# CDRon_IMU-BAT.net
KiCad netlist of a schematic drawn in Altium Designer
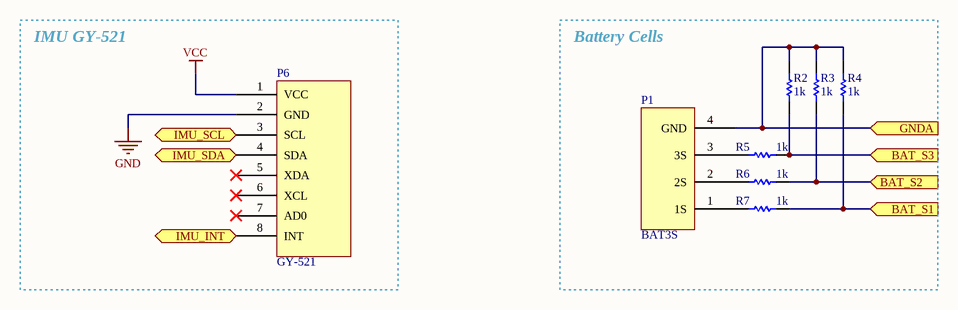
[diagram p0: CDRon_IMU-BAT.SchDoc]

(export (version "E")
  (design (tool "Eeschema 10.0.6"))
  (components
    (comp (ref "P1") (value "BAT3S") (footprint "BAT3S") (libsource (lib "CDRon_lib") (part "BAT3S")))
    (comp (ref "P6") (value "GY-521") (footprint "GY-521") (libsource (lib "CDRon_lib") (part "GY-521")))
    (comp (ref "R2")
      (value "1k")
      (footprint "R 1206")
      (description "Resistencia")
      (fields (field (name ".CREATOR") "SR"))
      (libsource (lib "CDRon_lib") (part "R"))
    )
    (comp (ref "R3")
      (value "1k")
      (footprint "R 1206")
      (description "Resistencia")
      (fields (field (name ".CREATOR") "SR"))
      (libsource (lib "CDRon_lib") (part "R"))
    )
    (comp (ref "R4")
      (value "1k")
      (footprint "R 1206")
      (description "Resistencia")
      (fields (field (name ".CREATOR") "SR"))
      (libsource (lib "CDRon_lib") (part "R"))
    )
    (comp (ref "R5")
      (value "1k")
      (footprint "R 1206")
      (description "Resistencia")
      (fields (field (name ".CREATOR") "SR"))
      (libsource (lib "CDRon_lib") (part "R"))
    )
    (comp (ref "R6")
      (value "1k")
      (footprint "R 1206")
      (description "Resistencia")
      (fields (field (name ".CREATOR") "SR"))
      (libsource (lib "CDRon_lib") (part "R"))
    )
    (comp (ref "R7")
      (value "1k")
      (footprint "R 1206")
      (description "Resistencia")
      (fields (field (name ".CREATOR") "SR"))
      (libsource (lib "CDRon_lib") (part "R"))
    )
  )
  (nets
    (net (code "1") (name "/BAT_S1") (class "Default")
      (node (ref "R4") (pin "1") (pinfunction "1_1") (pintype "passive"))
      (node (ref "R7") (pin "2") (pinfunction "2_2") (pintype "passive"))
    )
    (net (code "2") (name "/BAT_S2") (class "Default")
      (node (ref "R3") (pin "1") (pinfunction "1_1") (pintype "passive"))
      (node (ref "R6") (pin "2") (pinfunction "2_2") (pintype "passive"))
    )
    (net (code "3") (name "/BAT_S3") (class "Default")
      (node (ref "R2") (pin "1") (pinfunction "1_1") (pintype "passive"))
      (node (ref "R5") (pin "2") (pinfunction "2_2") (pintype "passive"))
    )
    (net (code "4") (name "/GNDA") (class "Default")
      (node (ref "P1") (pin "4") (pinfunction "GND_4") (pintype "passive"))
      (node (ref "R2") (pin "2") (pinfunction "2_2") (pintype "passive"))
      (node (ref "R3") (pin "2") (pinfunction "2_2") (pintype "passive"))
      (node (ref "R4") (pin "2") (pinfunction "2_2") (pintype "passive"))
    )
    (net (code "5") (name "/IMU_INT") (class "Default")
      (node (ref "P6") (pin "8") (pinfunction "INT_8") (pintype "passive"))
    )
    (net (code "6") (name "/IMU_SCL") (class "Default")
      (node (ref "P6") (pin "3") (pinfunction "SCL_3") (pintype "passive"))
    )
    (net (code "7") (name "/IMU_SDA") (class "Default")
      (node (ref "P6") (pin "4") (pinfunction "SDA_4") (pintype "passive"))
    )
    (net (code "8") (name "GND") (class "Default")
      (node (ref "P6") (pin "2") (pinfunction "GND_2") (pintype "passive"))
    )
    (net (code "9") (name "Net-(P1-1S)") (class "Default")
      (node (ref "P1") (pin "1") (pinfunction "1S_1") (pintype "passive"))
      (node (ref "R7") (pin "1") (pinfunction "1_1") (pintype "passive"))
    )
    (net (code "10") (name "Net-(P1-2S)") (class "Default")
      (node (ref "P1") (pin "2") (pinfunction "2S_2") (pintype "passive"))
      (node (ref "R6") (pin "1") (pinfunction "1_1") (pintype "passive"))
    )
    (net (code "11") (name "Net-(P1-3S)") (class "Default")
      (node (ref "P1") (pin "3") (pinfunction "3S_3") (pintype "passive"))
      (node (ref "R5") (pin "1") (pinfunction "1_1") (pintype "passive"))
    )
    (net (code "12") (name "VCC") (class "Default")
      (node (ref "P6") (pin "1") (pinfunction "VCC_1") (pintype "passive"))
    )
    (net (code "13") (name "unconnected-(P6-AD0-Pad7)") (class "Default")
      (node (ref "P6") (pin "7") (pinfunction "AD0_7") (pintype "passive+no_connect"))
    )
    (net (code "14") (name "unconnected-(P6-XCL-Pad6)") (class "Default")
      (node (ref "P6") (pin "6") (pinfunction "XCL_6") (pintype "passive+no_connect"))
    )
    (net (code "15") (name "unconnected-(P6-XDA-Pad5)") (class "Default")
      (node (ref "P6") (pin "5") (pinfunction "XDA_5") (pintype "passive+no_connect"))
    )
  )
)
